# Main.net
KiCad netlist of a schematic drawn in Altium Designer
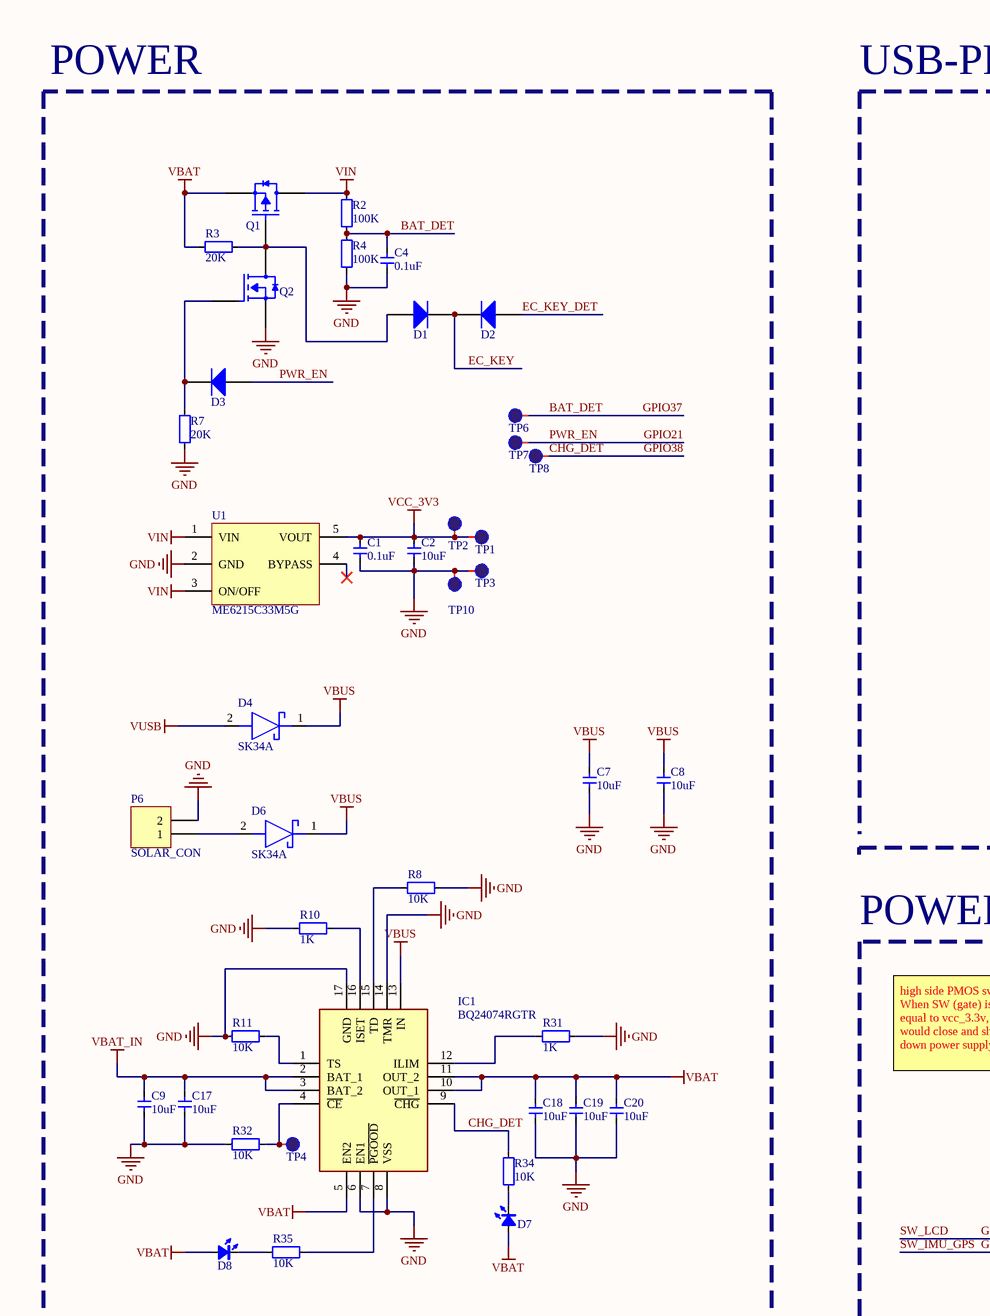
[diagram p0: Main.SchDoc, top left]
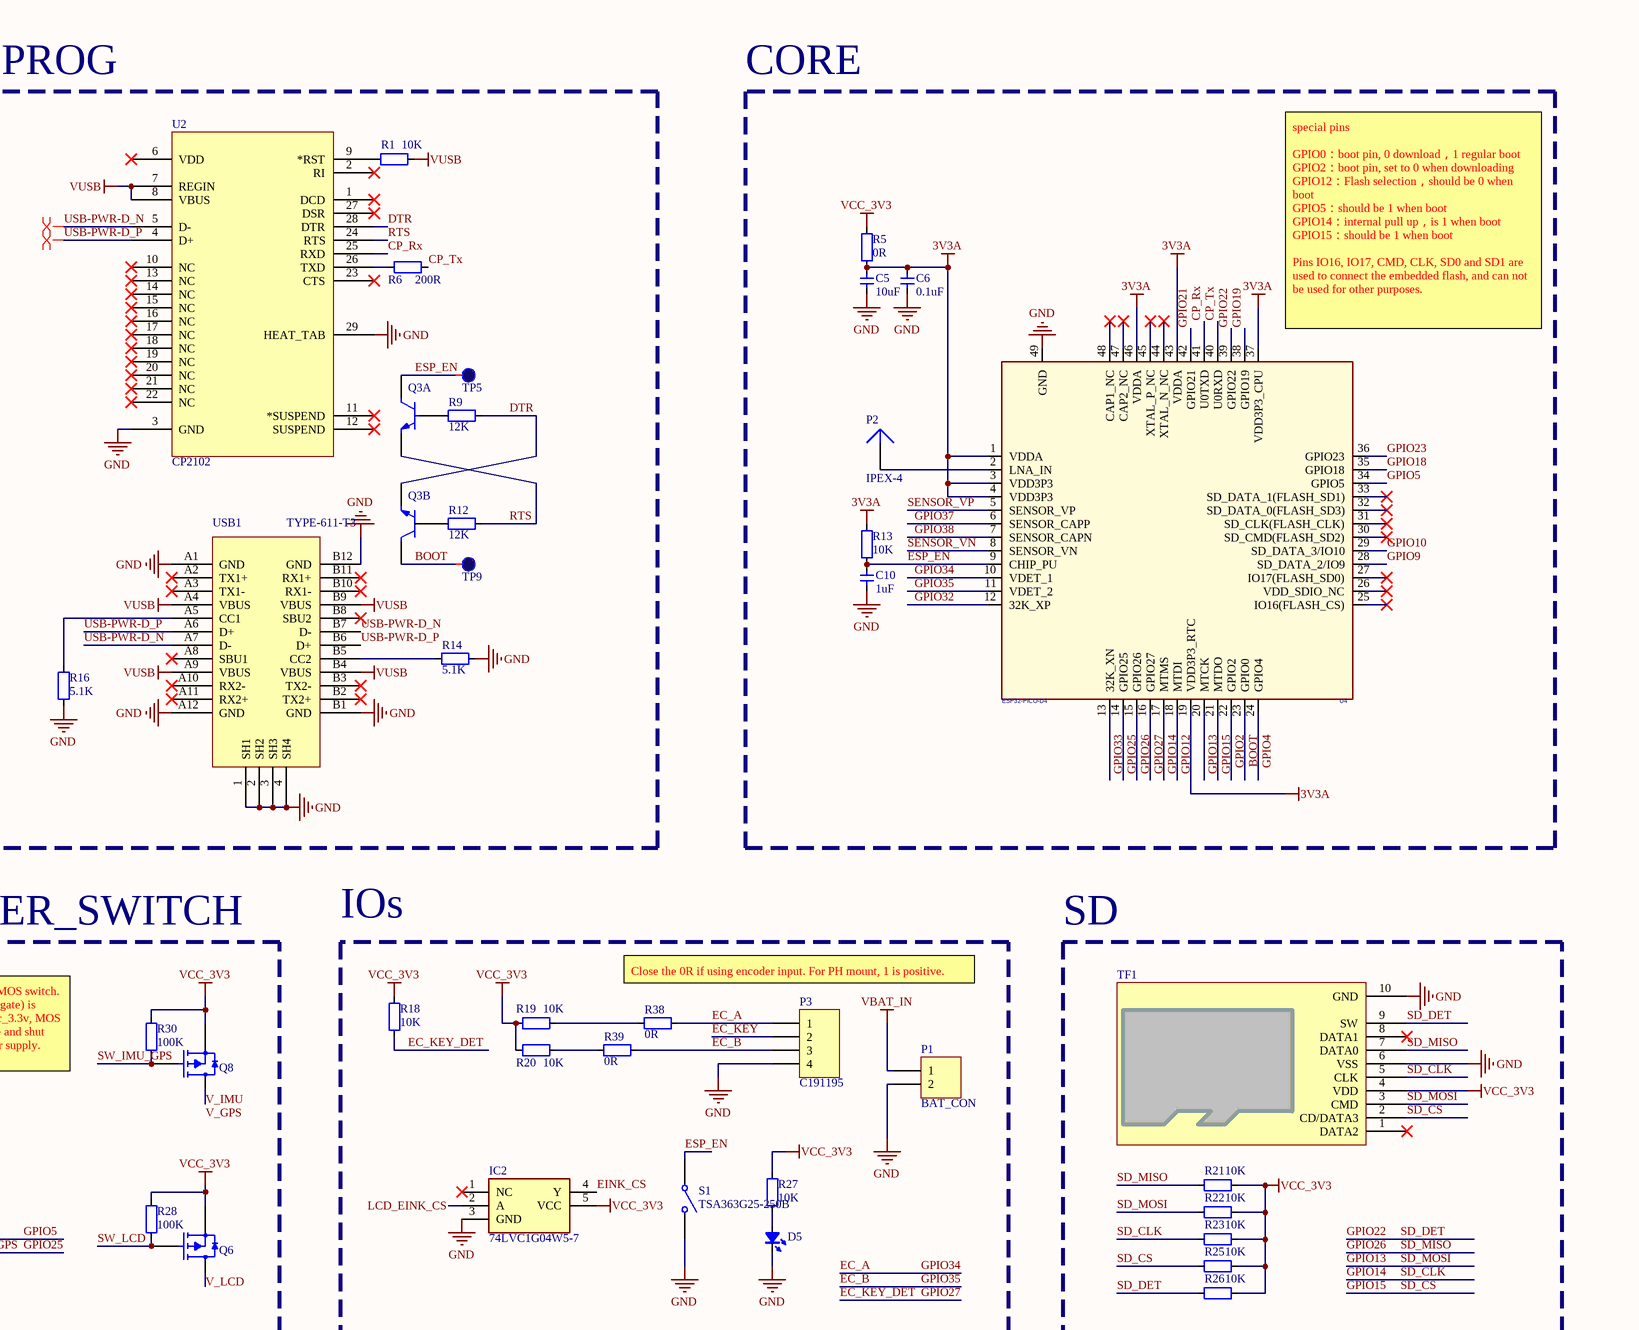
[diagram p1: Main.SchDoc, top right]
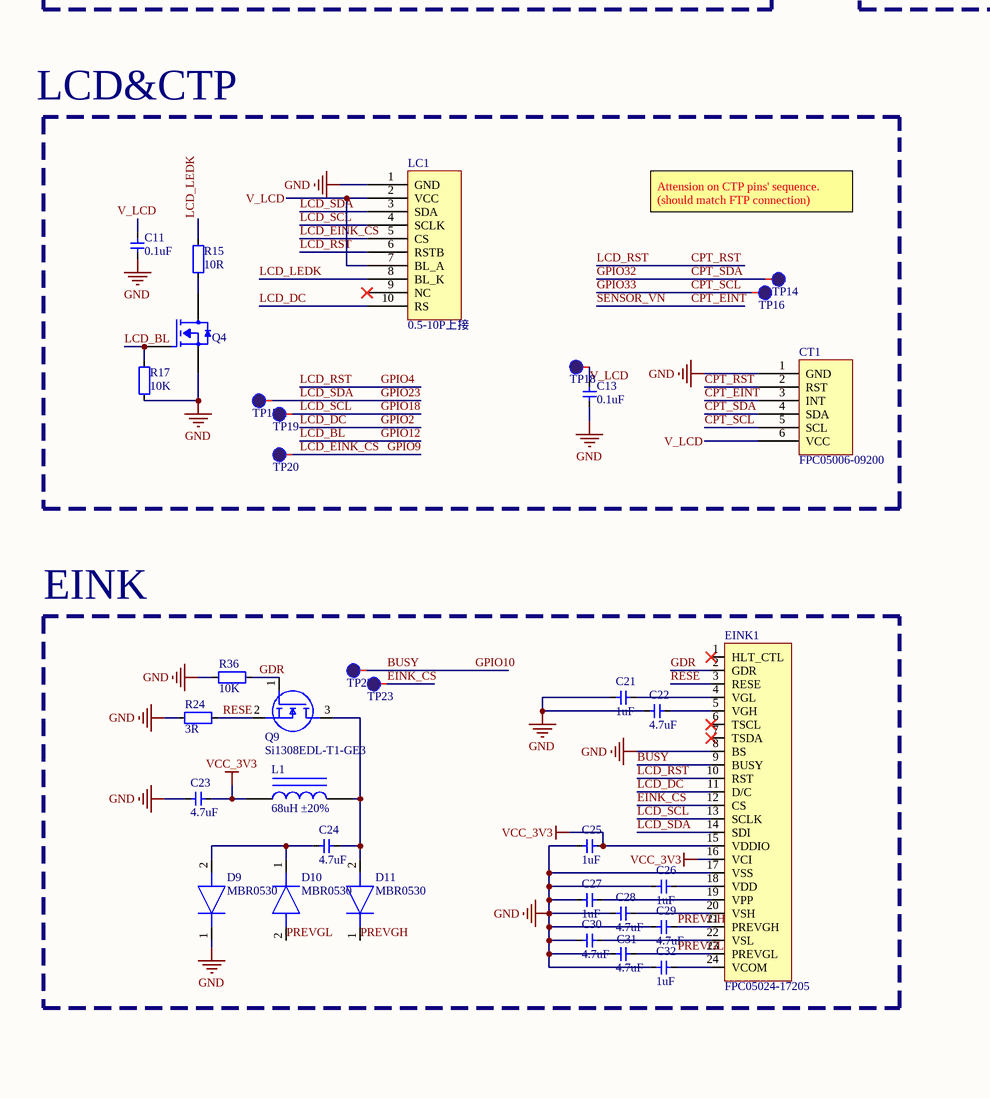
[diagram p2: Main.SchDoc, bottom left]
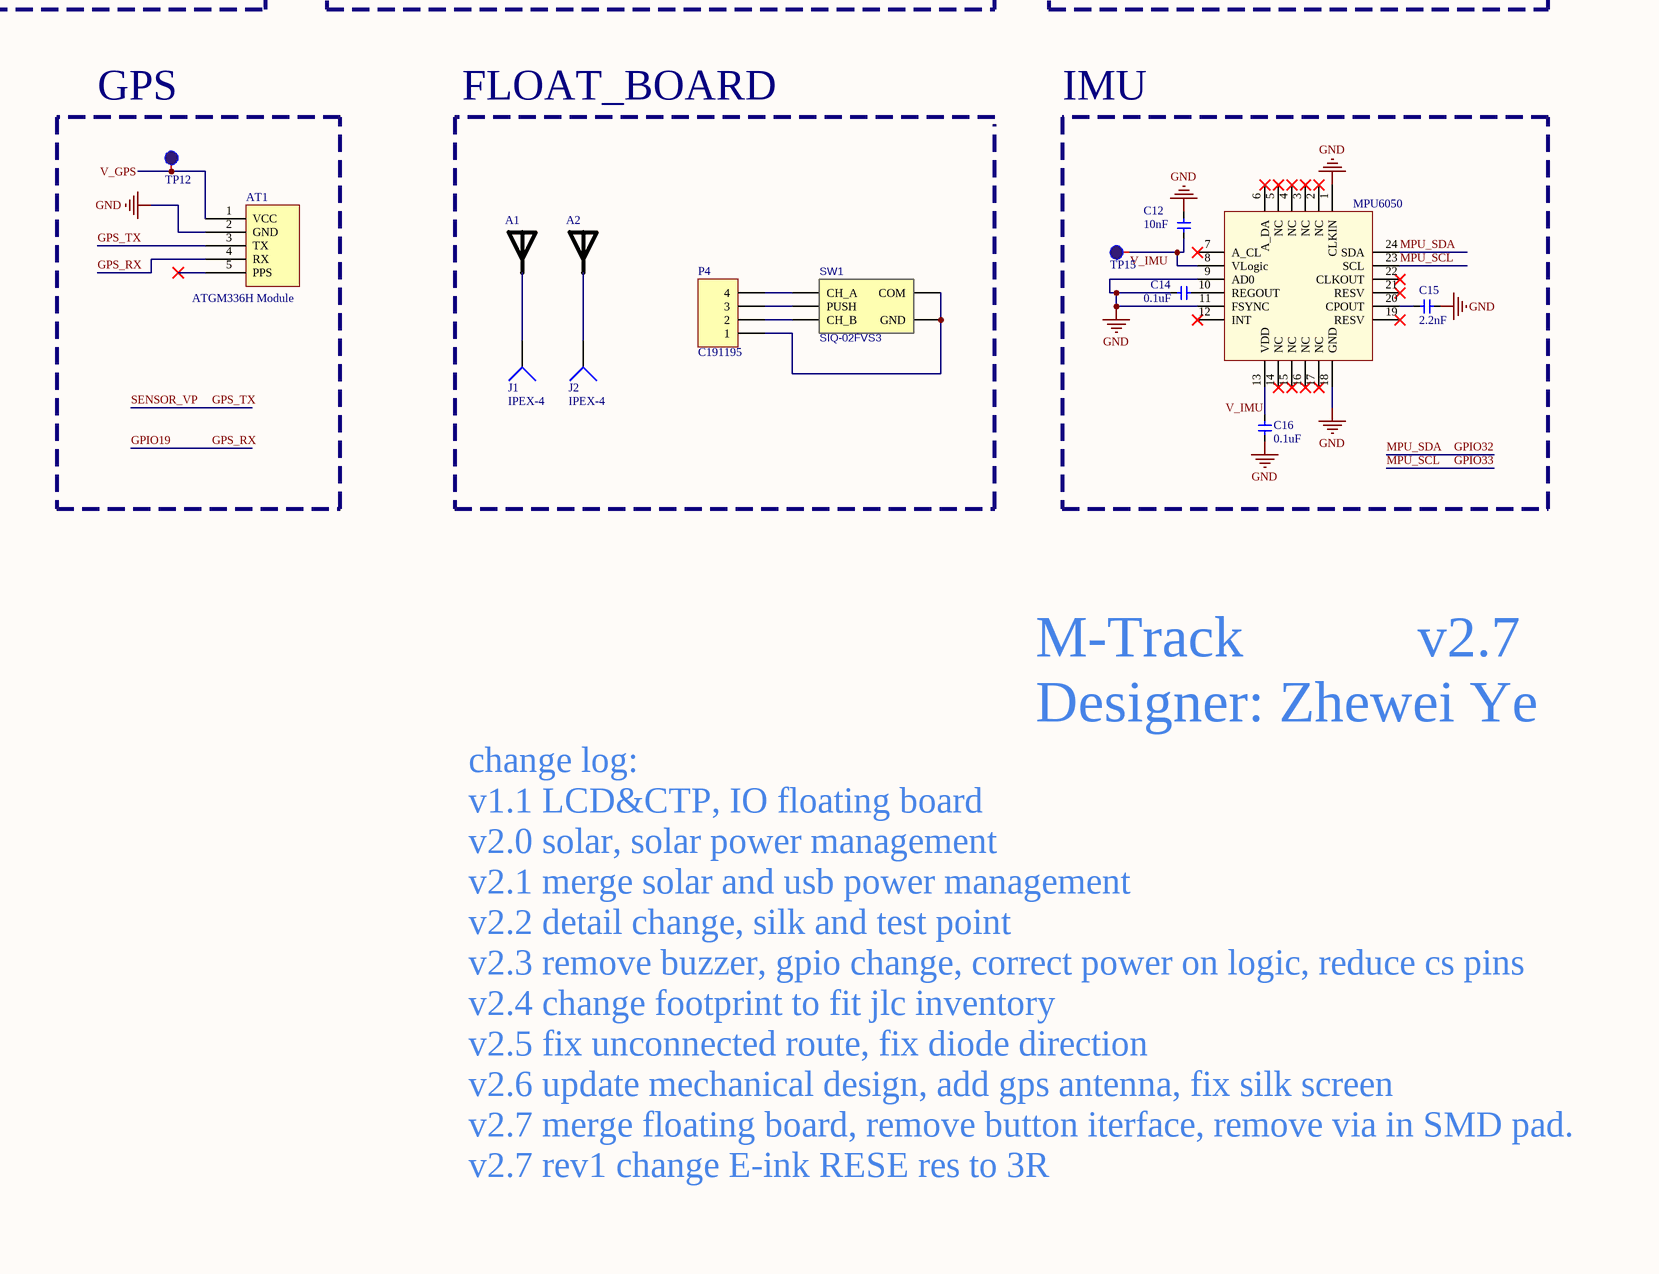
[diagram p3: Main.SchDoc, bottom right]

(export (version "E")
  (design (tool "Eeschema 10.0.6"))
  (components
    (comp (ref "A1")
      (value "AN2051-245")
      (footprint "ANT-Rainsun-AN5120")
      (description "footprint: 2051")
      (fields (field (name "LCSC PART #") "C99727"))
      (libsource (lib "Peak") (part "ANT-Rainsun-AP5120"))
    )
    (comp (ref "A2")
      (value "AN2051-245")
      (footprint "ANT-Rainsun-AN5120")
      (description "footprint: 2051")
      (fields (field (name "LCSC PART #") "C99727"))
      (libsource (lib "Peak") (part "ANT-Rainsun-AP5120"))
    )
    (comp (ref "AT1")
      (value "ATGM336H Module")
      (footprint "PCBComponent_1")
      (libsource (lib "ATGM336H") (part "ATGM336H Module"))
    )
    (comp (ref "C1")
      (value "0.1uF")
      (footprint "CAP_0402")
      (description "Capacitor")
      (libsource (lib "MyPcbLib") (part "电容-0402"))
    )
    (comp (ref "C2")
      (value "10uF")
      (footprint "CAP_0402")
      (description "Capacitor")
      (libsource (lib "MyPcbLib") (part "电容-0402"))
    )
    (comp (ref "C4")
      (value "0.1uF")
      (footprint "CAP_0402")
      (description "Capacitor")
      (libsource (lib "MyPcbLib") (part "电容-0402"))
    )
    (comp (ref "C5")
      (value "10uF")
      (footprint "CAP_0402")
      (description "Capacitor")
      (libsource (lib "MyPcbLib") (part "电容-0402"))
    )
    (comp (ref "C6")
      (value "0.1uF")
      (footprint "CAP_0402")
      (description "Capacitor")
      (libsource (lib "MyPcbLib") (part "电容-0402"))
    )
    (comp (ref "C7")
      (value "10uF")
      (footprint "CAP_0402")
      (description "Capacitor")
      (libsource (lib "MyPcbLib") (part "电容-0402"))
    )
    (comp (ref "C8")
      (value "10uF")
      (footprint "CAP_0402")
      (description "Capacitor")
      (libsource (lib "MyPcbLib") (part "电容-0402"))
    )
    (comp (ref "C9")
      (value "10uF")
      (footprint "CAP_0402")
      (description "Capacitor")
      (libsource (lib "MyPcbLib") (part "电容-0402"))
    )
    (comp (ref "C10")
      (value "1uF")
      (footprint "CAP_0402")
      (description "Capacitor")
      (fields (field (name "LCSC PART #") "C52923"))
      (libsource (lib "MyPcbLib") (part "电容-0402"))
    )
    (comp (ref "C11")
      (value "0.1uF")
      (footprint "CAP_0402")
      (description "Capacitor")
      (libsource (lib "MyPcbLib") (part "电容-0402"))
    )
    (comp (ref "C12")
      (value "10nF")
      (footprint "CAP_0402")
      (description "Capacitor")
      (libsource (lib "MyPcbLib") (part "电容-0402"))
    )
    (comp (ref "C13")
      (value "0.1uF")
      (footprint "CAP_0402")
      (description "Capacitor")
      (libsource (lib "MyPcbLib") (part "电容-0402"))
    )
    (comp (ref "C14")
      (value "0.1uF")
      (footprint "CAP_0402")
      (description "Capacitor")
      (libsource (lib "MyPcbLib") (part "电容-0402"))
    )
    (comp (ref "C15")
      (value "2.2nF")
      (footprint "CAP_0402")
      (description "Capacitor")
      (libsource (lib "MyPcbLib") (part "电容-0402"))
    )
    (comp (ref "C16")
      (value "0.1uF")
      (footprint "CAP_0402")
      (description "Capacitor")
      (libsource (lib "MyPcbLib") (part "电容-0402"))
    )
    (comp (ref "C17")
      (value "10uF")
      (footprint "CAP_0402")
      (description "Capacitor")
      (libsource (lib "MyPcbLib") (part "电容-0402"))
    )
    (comp (ref "C18")
      (value "10uF")
      (footprint "CAP_0402")
      (description "Capacitor")
      (libsource (lib "MyPcbLib") (part "电容-0402"))
    )
    (comp (ref "C19")
      (value "10uF")
      (footprint "CAP_0402")
      (description "Capacitor")
      (libsource (lib "MyPcbLib") (part "电容-0402"))
    )
    (comp (ref "C20")
      (value "10uF")
      (footprint "CAP_0402")
      (description "Capacitor")
      (libsource (lib "MyPcbLib") (part "电容-0402"))
    )
    (comp (ref "C21")
      (value "1uF")
      (footprint "CAP_0402")
      (description "Capacitor")
      (fields (field (name "LCSC PART #") "C52923"))
      (libsource (lib "MyPcbLib") (part "电容-0402"))
    )
    (comp (ref "C22")
      (value "4.7uF")
      (footprint "CAP_0402")
      (description "Capacitor")
      (libsource (lib "MyPcbLib") (part "电容-0402"))
    )
    (comp (ref "C23")
      (value "4.7uF")
      (footprint "CAP_0402")
      (description "Capacitor")
      (libsource (lib "MyPcbLib") (part "电容-0402"))
    )
    (comp (ref "C24")
      (value "4.7uF")
      (footprint "CAP_0402")
      (description "Capacitor")
      (libsource (lib "MyPcbLib") (part "电容-0402"))
    )
    (comp (ref "C25")
      (value "1uF")
      (footprint "CAP_0402")
      (description "Capacitor")
      (fields (field (name "LCSC PART #") "C52923"))
      (libsource (lib "MyPcbLib") (part "电容-0402"))
    )
    (comp (ref "C26")
      (value "1uF")
      (footprint "CAP_0402")
      (description "Capacitor")
      (fields (field (name "LCSC PART #") "C52923"))
      (libsource (lib "MyPcbLib") (part "电容-0402"))
    )
    (comp (ref "C27")
      (value "1uF")
      (footprint "CAP_0402")
      (description "Capacitor")
      (fields (field (name "LCSC PART #") "C52923"))
      (libsource (lib "MyPcbLib") (part "电容-0402"))
    )
    (comp (ref "C28")
      (value "4.7uF")
      (footprint "CAP_0402")
      (description "Capacitor")
      (libsource (lib "MyPcbLib") (part "电容-0402"))
    )
    (comp (ref "C29")
      (value "4.7uF")
      (footprint "CAP_0402")
      (description "Capacitor")
      (libsource (lib "MyPcbLib") (part "电容-0402"))
    )
    (comp (ref "C30")
      (value "4.7uF")
      (footprint "CAP_0402")
      (description "Capacitor")
      (libsource (lib "MyPcbLib") (part "电容-0402"))
    )
    (comp (ref "C31")
      (value "4.7uF")
      (footprint "CAP_0402")
      (description "Capacitor")
      (libsource (lib "MyPcbLib") (part "电容-0402"))
    )
    (comp (ref "C32")
      (value "1uF")
      (footprint "CAP_0402")
      (description "Capacitor")
      (fields (field (name "LCSC PART #") "C52923"))
      (libsource (lib "MyPcbLib") (part "电容-0402"))
    )
    (comp (ref "CT1")
      (value "FPC05006-09200")
      (footprint "FPC0.5-WT-6P")
      (description "下接6p")
      (libsource (lib "Bike_Comp") (part "CTP"))
    )
    (comp (ref "D1")
      (value "B5819W")
      (footprint "SOD-323")
      (description "40V")
      (fields (field (name "LCSC PART #") "C8598"))
      (libsource (lib "MyPcbLib") (part "二极管-5819W"))
    )
    (comp (ref "D2")
      (value "B5819W")
      (footprint "SOD-323")
      (description "40V")
      (fields (field (name "LCSC PART #") "C8598"))
      (libsource (lib "MyPcbLib") (part "二极管-5819W"))
    )
    (comp (ref "D3")
      (value "B5819W")
      (footprint "SOD-323")
      (description "40V")
      (fields (field (name "LCSC PART #") "C8598"))
      (libsource (lib "MyPcbLib") (part "二极管-5819W"))
    )
    (comp (ref "D4")
      (value "SK34A")
      (footprint "SMA")
      (description "GOOD_ARK Schottky Diode")
      (fields
        (field (name "MANUFACTURER_PART_NUMBER") "SK34AFL-TP")
        (field (name "MOUSER PART NUMBER") "833-SK34AFL-TP")
      )
      (libsource (lib "*") (part "SK34AFL-TP"))
    )
    (comp (ref "D5")
      (value "LTST-C281KGKT")
      (footprint "LED_0402_RED")
      (description "GREEN_LED")
      (fields (field (name "LCSC PART #") "C160479"))
      (libsource (lib "") (part "LED_0402_1"))
    )
    (comp (ref "D6")
      (value "SK34A")
      (footprint "SMA")
      (description "GOOD_ARK Schottky Diode")
      (fields
        (field (name "MANUFACTURER_PART_NUMBER") "SK34AFL-TP")
        (field (name "MOUSER PART NUMBER") "833-SK34AFL-TP")
      )
      (libsource (lib "*") (part "SK34AFL-TP"))
    )
    (comp (ref "D7")
      (value "16-213/SDRC/S530-A3/TR8")
      (footprint "LED_0402_RED")
      (description "RED_LED")
      (fields (field (name "LCSC PART #") "C71911"))
      (libsource (lib "KitSprout") (part "LED_0402"))
    )
    (comp (ref "D8")
      (value "LTST-C281KGKT")
      (footprint "LED_0402_RED")
      (description "GREEN_LED")
      (fields (field (name "LCSC PART #") "C160479"))
      (libsource (lib "") (part "LED_0402_2"))
    )
    (comp (ref "D9")
      (value "MBR0530")
      (footprint "SamacSys:SOD3716X135N")
      (description "Diode")
      (fields (field (name "MOUSER PART NUMBER") "512-MBR0530") (field (name "LCSC PART #") "C77336"))
      (libsource (lib "*") (part "MBR0530"))
    )
    (comp (ref "D10")
      (value "MBR0530")
      (footprint "SamacSys:SOD3716X135N")
      (description "Diode")
      (fields (field (name "MOUSER PART NUMBER") "512-MBR0530") (field (name "LCSC PART #") "C77336"))
      (libsource (lib "*") (part "MBR0530"))
    )
    (comp (ref "D11")
      (value "MBR0530")
      (footprint "SamacSys:SOD3716X135N")
      (description "Diode")
      (fields (field (name "MOUSER PART NUMBER") "512-MBR0530") (field (name "LCSC PART #") "C77336"))
      (libsource (lib "*") (part "MBR0530"))
    )
    (comp (ref "EINK1")
      (value "FPC05024-17205")
      (footprint "FPC0.5-WT-24P")
      (description "上接24p")
      (libsource (lib "Bike_Comp") (part "EINK"))
    )
    (comp (ref "IC1")
      (value "BQ24074RGTR")
      (footprint "SamacSys:QFN50P300X300X100-17N-D")
      (description "Integrated Circuit")
      (fields (field (name "MOUSER PART NUMBER") "595-BQ24074RGTR"))
      (libsource (lib "*") (part "BQ24074RGTR"))
    )
    (comp (ref "IC2")
      (value "74LVC1G04W5-7")
      (footprint "SamacSys:SOT95P285X140-5N")
      (description "Integrated Circuit")
      (fields (field (name "MOUSER PART NUMBER") "621-74LVC1G04W5-7"))
      (libsource (lib "*") (part "74LVC1G04W5-7"))
    )
    (comp (ref "J1")
      (value "IPEX-4")
      (footprint "COAXIAL/SMD/CON/V/I-PEX/W08-5801")
      (description "Socket")
      (fields (field (name "PUBLISHER") "Altium Limited"))
      (libsource (lib "Miscellaneous Connectors") (part "Socket"))
    )
    (comp (ref "J2")
      (value "IPEX-4")
      (footprint "COAXIAL/SMD/CON/V/I-PEX/W08-5801")
      (description "Socket")
      (fields (field (name "PUBLISHER") "Altium Limited"))
      (libsource (lib "Miscellaneous Connectors") (part "Socket"))
    )
    (comp (ref "L1")
      (value "68uH ±20%")
      (footprint "SWPA3015")
      (description "Magnetic-Core Inductor")
      (fields (field (name "LCSC PART #") "C2925423") (field (name "PUBLISHER") "Altium Limited"))
      (libsource (lib "Miscellaneous Devices") (part "Inductor Iron"))
    )
    (comp (ref "LC1")
      (value "0.5-10P上接")
      (footprint "FPC0.5-WT-10P")
      (description "上接10p")
      (fields (field (name "LCSC PART #") "C11085"))
      (libsource (lib "Bike_Comp") (part "LCD"))
    )
    (comp (ref "P1")
      (value "BAT_CON")
      (footprint "PH2.0-W-2P")
      (description "PH2.0-2P-LT")
      (fields (field (name "PUBLISHER") "Altium Limited"))
      (libsource (lib "Miscellaneous Connectors") (part "Header 2"))
    )
    (comp (ref "P2")
      (value "IPEX-4")
      (footprint "COAXIAL/SMD/CON/V/I-PEX/W08-5801")
      (description "Plug")
      (fields (field (name "PUBLISHER") "Altium Limited"))
      (libsource (lib "Miscellaneous Connectors") (part "Plug"))
    )
    (comp (ref "P3")
      (value "C191195")
      (footprint "FPC0.5-WT-4P")
      (description "Header, 4-Pin")
      (fields (field (name "PUBLISHER") "Altium Limited"))
      (libsource (lib "Miscellaneous Connectors") (part "Header 4"))
    )
    (comp (ref "P4")
      (value "C191195")
      (footprint "FPC0.5-WT-4P")
      (description "Header, 4-Pin")
      (fields (field (name "PUBLISHER") "Altium Limited"))
      (libsource (lib "") (part "Header 4_1"))
    )
    (comp (ref "P6")
      (value "SOLAR_CON")
      (footprint "PH2.0-W-2P")
      (description "PH2.0-2P-LT")
      (fields (field (name "PUBLISHER") "Altium Limited"))
      (libsource (lib "") (part "Header 2_1"))
    )
    (comp (ref "Q1")
      (value "AO3401A")
      (footprint "SOT23-3")
      (description "P-MOS")
      (fields (field (name "LCSC PART #") "C15127"))
      (libsource (lib "MyPcbLib") (part "AO3401A"))
    )
    (comp (ref "Q2")
      (value "AO3400A")
      (footprint "SOT23-3")
      (description "N-MOS")
      (libsource (lib "MyPcbLib") (part "AO3400A"))
    )
    (comp (ref "Q3")
      (value "EMX1T2R")
      (footprint "SOT563-6")
      (libsource (lib "MyPcbLib") (part "BC847BVC-7"))
    )
    (comp (ref "Q4")
      (value "AO3400A")
      (footprint "SOT23-3")
      (description "N-MOS")
      (libsource (lib "Bike_Comp") (part "AO3400A"))
    )
    (comp (ref "Q6")
      (value "AO3401A")
      (footprint "SOT23-3")
      (description "P-MOS")
      (fields (field (name "LCSC PART #") "C15127"))
      (libsource (lib "MyPcbLib") (part "AO3401A"))
    )
    (comp (ref "Q8")
      (value "AO3401A")
      (footprint "SOT23-3")
      (description "P-MOS")
      (fields (field (name "LCSC PART #") "C15127"))
      (libsource (lib "MyPcbLib") (part "AO3401A"))
    )
    (comp (ref "Q9")
      (value "Si1308EDL-T1-GE3")
      (footprint "SamacSys:SOT65P210X110-3N")
      (description "MOSFET (N-Channel)")
      (fields
        (field (name "MOUSER PART NUMBER") "78-SI1308EDL-T1-GE3")
        (field (name "ARROW PART NUMBER") "SI1308EDL-T1-GE3")
      )
      (libsource (lib "*") (part "Si1308EDL-T1-GE3"))
    )
    (comp (ref "R1")
      (value "10K")
      (footprint "RES_0402")
      (description "Resistor")
      (libsource (lib "") (part "电阻-0402_2"))
    )
    (comp (ref "R2")
      (value "100K")
      (footprint "RES_0402")
      (description "Resistor")
      (libsource (lib "") (part "电阻-0402_1"))
    )
    (comp (ref "R3")
      (value "20K")
      (footprint "RES_0402")
      (description "Resistor")
      (libsource (lib "") (part "电阻-0402_3"))
    )
    (comp (ref "R4")
      (value "100K")
      (footprint "RES_0402")
      (description "Resistor")
      (libsource (lib "") (part "电阻-0402_1"))
    )
    (comp (ref "R5")
      (value "0R")
      (footprint "RES_0402")
      (description "Resistor")
      (libsource (lib "MyPcbLib") (part "电阻-0402"))
    )
    (comp (ref "R6")
      (value "200R")
      (footprint "RES_0402")
      (description "Resistor")
      (libsource (lib "") (part "电阻-0402_2"))
    )
    (comp (ref "R7")
      (value "20K")
      (footprint "RES_0402")
      (description "Resistor")
      (libsource (lib "") (part "电阻-0402_1"))
    )
    (comp (ref "R8")
      (value "10K")
      (footprint "RES_0402")
      (description "Resistor")
      (libsource (lib "") (part "电阻-0402_2"))
    )
    (comp (ref "R9")
      (value "12K")
      (footprint "RES_0402")
      (description "Resistor")
      (fields (field (name "LCSC PART #") "C25752"))
      (libsource (lib "") (part "电阻-0402_2"))
    )
    (comp (ref "R10")
      (value "1K")
      (footprint "RES_0402")
      (description "Resistor")
      (libsource (lib "") (part "电阻-0402_3"))
    )
    (comp (ref "R11")
      (value "10K")
      (footprint "RES_0402")
      (description "Resistor")
      (libsource (lib "") (part "电阻-0402_2"))
    )
    (comp (ref "R12")
      (value "12K")
      (footprint "RES_0402")
      (description "Resistor")
      (fields (field (name "LCSC PART #") "C25752"))
      (libsource (lib "") (part "电阻-0402_2"))
    )
    (comp (ref "R13")
      (value "10K")
      (footprint "RES_0402")
      (description "Resistor")
      (libsource (lib "MyPcbLib") (part "电阻-0402"))
    )
    (comp (ref "R14")
      (value "5.1K")
      (footprint "RES_0402")
      (description "Resistor")
      (libsource (lib "") (part "电阻-0402_2"))
    )
    (comp (ref "R15")
      (value "10R")
      (footprint "RES_0402")
      (description "Resistor")
      (fields (field (name "LCSC PART #") "C25077"))
      (libsource (lib "") (part "电阻-0402_1"))
    )
    (comp (ref "R16")
      (value "5.1K")
      (footprint "RES_0402")
      (description "Resistor")
      (libsource (lib "MyPcbLib") (part "电阻-0402"))
    )
    (comp (ref "R17")
      (value "10K")
      (footprint "RES_0402")
      (description "Resistor")
      (libsource (lib "") (part "电阻-0402_1"))
    )
    (comp (ref "R18")
      (value "10K")
      (footprint "RES_0402")
      (description "Resistor")
      (libsource (lib "MyPcbLib") (part "电阻-0402"))
    )
    (comp (ref "R19")
      (value "10K")
      (footprint "RES_0402")
      (description "Resistor")
      (libsource (lib "") (part "电阻-0402_2"))
    )
    (comp (ref "R20")
      (value "10K")
      (footprint "RES_0402")
      (description "Resistor")
      (libsource (lib "") (part "电阻-0402_2"))
    )
    (comp (ref "R21")
      (value "10K")
      (footprint "RES_0402")
      (description "Resistor")
      (libsource (lib "") (part "电阻-0402_2"))
    )
    (comp (ref "R22")
      (value "10K")
      (footprint "RES_0402")
      (description "Resistor")
      (libsource (lib "") (part "电阻-0402_2"))
    )
    (comp (ref "R23")
      (value "10K")
      (footprint "RES_0402")
      (description "Resistor")
      (libsource (lib "") (part "电阻-0402_2"))
    )
    (comp (ref "R24")
      (value "3R")
      (footprint "RES_0402")
      (description "Resistor")
      (libsource (lib "") (part "电阻-0402_3"))
    )
    (comp (ref "R25")
      (value "10K")
      (footprint "RES_0402")
      (description "Resistor")
      (libsource (lib "") (part "电阻-0402_2"))
    )
    (comp (ref "R26")
      (value "10K")
      (footprint "RES_0402")
      (description "Resistor")
      (libsource (lib "") (part "电阻-0402_2"))
    )
    (comp (ref "R27")
      (value "10K")
      (footprint "RES_0402")
      (description "Resistor")
      (libsource (lib "") (part "电阻-0402_1"))
    )
    (comp (ref "R28")
      (value "100K")
      (footprint "RES_0402")
      (description "Resistor")
      (libsource (lib "") (part "电阻-0402_1"))
    )
    (comp (ref "R30")
      (value "100K")
      (footprint "RES_0402")
      (description "Resistor")
      (libsource (lib "") (part "电阻-0402_1"))
    )
    (comp (ref "R31")
      (value "1K")
      (footprint "RES_0402")
      (description "Resistor")
      (libsource (lib "") (part "电阻-0402_2"))
    )
    (comp (ref "R32")
      (value "10K")
      (footprint "RES_0402")
      (description "Resistor")
      (libsource (lib "") (part "电阻-0402_2"))
    )
    (comp (ref "R34")
      (value "10K")
      (footprint "RES_0402")
      (description "Resistor")
      (libsource (lib "") (part "电阻-0402_1"))
    )
    (comp (ref "R35")
      (value "10K")
      (footprint "RES_0402")
      (description "Resistor")
      (libsource (lib "") (part "电阻-0402_3"))
    )
    (comp (ref "R36")
      (value "10K")
      (footprint "RES_0402")
      (description "Resistor")
      (libsource (lib "") (part "电阻-0402_3"))
    )
    (comp (ref "R38")
      (value "0R")
      (footprint "RES_0402")
      (description "Resistor")
      (libsource (lib "") (part "电阻-0402_3"))
    )
    (comp (ref "R39")
      (value "0R")
      (footprint "RES_0402")
      (description "Resistor")
      (libsource (lib "") (part "电阻-0402_3"))
    )
    (comp (ref "S1")
      (value "TSA363G25-250B")
      (footprint "SW SMD-3*6*2.5")
      (description "Single-Pole, Single-Throw Switch")
      (fields (field (name "PUBLISHER") "Altium Limited"))
      (libsource (lib "Miscellaneous Devices") (part "SW-SPST"))
    )
    (comp (ref "SW1")
      (value "SIQ-02FVS3")
      (footprint "SIQ-02FVS3")
      (description "Rotary Encoder")
      (fields
        (field (name "BOM_SUPPLIER PART") "C1322543")
        (field (name "BOM_MANUFACTURER PART") "EC11E1534443")
        (field (name "CONTRIBUTOR") "LCSC")
      )
      (libsource (lib "MyPcbLib") (part "Rotary Encoder"))
    )
    (comp (ref "TF1")
      (value "TF-012D")
      (footprint "TF-SOCKET")
      (description "8脚自弹")
      (libsource (lib "MyPcbLib") (part "TF卡座"))
    )
    (comp (ref "TP1") (value "TP") (footprint "TP_SMD") (libsource (lib "BSPD_2019_V3") (part "TP")))
    (comp (ref "TP2") (value "TP") (footprint "TEST 1") (libsource (lib "BSPD_2019_V3") (part "TP")))
    (comp (ref "TP3") (value "TP") (footprint "TP_SMD") (libsource (lib "BSPD_2019_V3") (part "TP")))
    (comp (ref "TP4") (value "TP") (footprint "TEST 1") (libsource (lib "Bike_Comp") (part "TP")))
    (comp (ref "TP5") (value "TP") (footprint "TEST 1") (libsource (lib "Bike_Comp") (part "TP")))
    (comp (ref "TP6") (value "TP") (footprint "TEST 1") (libsource (lib "Bike_Comp") (part "TP")))
    (comp (ref "TP7") (value "TP") (footprint "TEST 1") (libsource (lib "Bike_Comp") (part "TP")))
    (comp (ref "TP8") (value "TP") (footprint "TEST 1") (libsource (lib "Bike_Comp") (part "TP")))
    (comp (ref "TP9") (value "TP") (footprint "TEST 1") (libsource (lib "Bike_Comp") (part "TP")))
    (comp (ref "TP10") (value "TP") (footprint "TP_SMD") (libsource (lib "BSPD_2019_V3") (part "TP")))
    (comp (ref "TP12") (value "TP") (footprint "TEST 1") (libsource (lib "Bike_Comp") (part "TP")))
    (comp (ref "TP14") (value "TP") (footprint "TEST 1") (libsource (lib "Bike_Comp") (part "TP")))
    (comp (ref "TP15") (value "TP") (footprint "TEST 1") (libsource (lib "Bike_Comp") (part "TP")))
    (comp (ref "TP16") (value "TP") (footprint "TEST 1") (libsource (lib "Bike_Comp") (part "TP")))
    (comp (ref "TP17") (value "TP") (footprint "TEST 1") (libsource (lib "Bike_Comp") (part "TP")))
    (comp (ref "TP18") (value "TP") (footprint "TEST 1") (libsource (lib "Bike_Comp") (part "TP")))
    (comp (ref "TP19") (value "TP") (footprint "TEST 1") (libsource (lib "Bike_Comp") (part "TP")))
    (comp (ref "TP20") (value "TP") (footprint "TEST 1") (libsource (lib "Bike_Comp") (part "TP")))
    (comp (ref "TP22") (value "TP") (footprint "TEST 1") (libsource (lib "Bike_Comp") (part "TP")))
    (comp (ref "TP23") (value "TP") (footprint "TEST 1") (libsource (lib "Bike_Comp") (part "TP")))
    (comp (ref "U1")
      (value "ME6215C33M5G")
      (footprint "SOT23-5")
      (description "LDO module changed, BYPASS now is NC")
      (libsource (lib "mLib") (part "LP2992"))
    )
    (comp (ref "U2")
      (value "CP2102")
      (footprint "QFN-28")
      (description "USB转TTL")
      (libsource (lib "mLib") (part "CP2102"))
    )
    (comp (ref "U4")
      (value "ESP32-PICO-D4")
      (footprint "QFN-48_7X7")
      (fields (field (name "LCSC PART #") "C193707"))
      (libsource (lib "Peak") (part "ESP32-PICO"))
    )
    (comp (ref "U5")
      (value "MPU6050")
      (footprint "QFN-24")
      (description "六轴传感器")
      (fields (field (name "LCSC PART #") "C24112"))
      (libsource (lib "mLib") (part "MPU6050"))
    )
    (comp (ref "USB1")
      (value "TYPE-611-T3")
      (footprint "USB-C-SMD_16P")
      (description "16pin")
      (libsource (lib "MyPcbLib") (part "USB-Type-C-TOP"))
    )
  )
  (nets
    (net (code "1") (name "/BAT_DET") (class "Default")
      (node (ref "C4") (pin "2") (pinfunction "2_2") (pintype "passive"))
      (node (ref "R2") (pin "1") (pinfunction "1_1") (pintype "passive"))
      (node (ref "R4") (pin "2") (pinfunction "2_2") (pintype "passive"))
      (node (ref "TP6") (pin "0") (pinfunction "0_0") (pintype "passive"))
      (node (ref "U4") (pin "6") (pinfunction "SENSOR_CAPP_6") (pintype "passive"))
    )
    (net (code "2") (name "/BOOT") (class "Default")
      (node (ref "Q3") (pin "3") (pinfunction "C2_3") (pintype "passive"))
      (node (ref "TP9") (pin "0") (pinfunction "0_0") (pintype "passive"))
      (node (ref "U4") (pin "23") (pinfunction "GPIO0_23") (pintype "passive"))
    )
    (net (code "3") (name "/BUSY") (class "Default")
      (node (ref "EINK1") (pin "9") (pinfunction "BUSY_9") (pintype "passive"))
      (node (ref "TP22") (pin "0") (pinfunction "0_0") (pintype "passive"))
      (node (ref "U4") (pin "29") (pinfunction "SD_DATA_3/IO10_29") (pintype "passive"))
    )
    (net (code "4") (name "/CHG_DET") (class "Default")
      (node (ref "IC1") (pin "9") (pinfunction "~{CHG}_9") (pintype "passive"))
      (node (ref "R34") (pin "2") (pinfunction "2_2") (pintype "passive"))
      (node (ref "TP8") (pin "0") (pinfunction "0_0") (pintype "passive"))
      (node (ref "U4") (pin "7") (pinfunction "SENSOR_CAPN_7") (pintype "passive"))
    )
    (net (code "5") (name "/CPT_EINT") (class "Default")
      (node (ref "CT1") (pin "3") (pinfunction "INT_3") (pintype "passive"))
      (node (ref "U4") (pin "8") (pinfunction "SENSOR_VN_8") (pintype "passive"))
    )
    (net (code "6") (name "/CPT_RST") (class "Default")
      (node (ref "CT1") (pin "2") (pinfunction "RST_2") (pintype "passive"))
      (node (ref "EINK1") (pin "10") (pinfunction "RST_10") (pintype "passive"))
      (node (ref "LC1") (pin "6") (pinfunction "RSTB_6") (pintype "passive"))
      (node (ref "U4") (pin "24") (pinfunction "GPIO4_24") (pintype "passive"))
    )
    (net (code "7") (name "/CPT_SCL") (class "Default")
      (node (ref "CT1") (pin "5") (pinfunction "SCL_5") (pintype "passive"))
      (node (ref "TP16") (pin "0") (pinfunction "0_0") (pintype "passive"))
      (node (ref "U4") (pin "13") (pinfunction "32K_XN_13") (pintype "passive"))
      (node (ref "U5") (pin "23") (pinfunction "SCL_23") (pintype "passive"))
    )
    (net (code "8") (name "/CPT_SDA") (class "Default")
      (node (ref "CT1") (pin "4") (pinfunction "SDA_4") (pintype "passive"))
      (node (ref "TP14") (pin "0") (pinfunction "0_0") (pintype "passive"))
      (node (ref "U4") (pin "12") (pinfunction "32K_XP_12") (pintype "passive"))
      (node (ref "U5") (pin "24") (pinfunction "SDA_24") (pintype "passive"))
    )
    (net (code "9") (name "/CP_Rx") (class "Default")
      (node (ref "U2") (pin "25") (pinfunction "RXD_25") (pintype "passive"))
      (node (ref "U4") (pin "41") (pinfunction "U0TXD_41") (pintype "power_in"))
    )
    (net (code "10") (name "/CP_Tx") (class "Default")
      (node (ref "R6") (pin "1") (pinfunction "1_1") (pintype "passive"))
      (node (ref "U4") (pin "40") (pinfunction "U0RXD_40") (pintype "power_in"))
    )
    (net (code "11") (name "/DTR") (class "Default")
      (node (ref "Q3") (pin "4") (pinfunction "E2_4") (pintype "passive"))
      (node (ref "R9") (pin "1") (pinfunction "1_1") (pintype "passive"))
      (node (ref "U2") (pin "28") (pinfunction "DTR_28") (pintype "passive"))
    )
    (net (code "12") (name "/EC_A") (class "Default")
      (node (ref "P3") (pin "1") (pinfunction "1_1") (pintype "passive"))
      (node (ref "R38") (pin "2") (pinfunction "2_2") (pintype "passive"))
      (node (ref "U4") (pin "10") (pinfunction "VDET_1_10") (pintype "passive"))
    )
    (net (code "13") (name "/EC_B") (class "Default")
      (node (ref "P3") (pin "3") (pinfunction "3_3") (pintype "passive"))
      (node (ref "R39") (pin "2") (pinfunction "2_2") (pintype "passive"))
      (node (ref "U4") (pin "11") (pinfunction "VDET_2_11") (pintype "passive"))
    )
    (net (code "14") (name "/EC_KEY") (class "Default")
      (node (ref "D1") (pin "2") (pinfunction "K_2") (pintype "passive"))
      (node (ref "D2") (pin "2") (pinfunction "K_2") (pintype "passive"))
      (node (ref "P3") (pin "2") (pinfunction "2_2") (pintype "passive"))
    )
    (net (code "15") (name "/EC_KEY_DET") (class "Default")
      (node (ref "D2") (pin "1") (pinfunction "A_1") (pintype "passive"))
      (node (ref "R18") (pin "2") (pinfunction "2_2") (pintype "passive"))
      (node (ref "U4") (pin "16") (pinfunction "GPIO27_16") (pintype "passive"))
    )
    (net (code "16") (name "/EINK_CS") (class "Default")
      (node (ref "EINK1") (pin "12") (pinfunction "CS_12") (pintype "passive"))
      (node (ref "IC2") (pin "4") (pinfunction "Y_4") (pintype "passive"))
      (node (ref "TP23") (pin "0") (pinfunction "0_0") (pintype "passive"))
    )
    (net (code "17") (name "/ESP_EN") (class "Default")
      (node (ref "C10") (pin "1") (pinfunction "1_1") (pintype "passive"))
      (node (ref "Q3") (pin "6") (pinfunction "C1_6") (pintype "passive"))
      (node (ref "R13") (pin "2") (pinfunction "2_2") (pintype "passive"))
      (node (ref "S1") (pin "1") (pinfunction "COMMON_1") (pintype "passive"))
      (node (ref "TP5") (pin "0") (pinfunction "0_0") (pintype "passive"))
      (node (ref "U4") (pin "9") (pinfunction "CHIP_PU_9") (pintype "passive"))
    )
    (net (code "18") (name "/GDR") (class "Default")
      (node (ref "EINK1") (pin "2") (pinfunction "GDR_2") (pintype "passive"))
      (node (ref "Q9") (pin "1") (pinfunction "G_1") (pintype "passive"))
      (node (ref "R36") (pin "2") (pinfunction "2_2") (pintype "passive"))
    )
    (net (code "19") (name "/GPIO2") (class "Default")
      (node (ref "EINK1") (pin "11") (pinfunction "D/C_11") (pintype "passive"))
      (node (ref "LC1") (pin "10") (pinfunction "RS_10") (pintype "passive"))
      (node (ref "U4") (pin "22") (pinfunction "GPIO2_22") (pintype "passive"))
    )
    (net (code "20") (name "/GPIO5") (class "Default")
      (node (ref "Q6") (pin "1") (pinfunction "G_1") (pintype "passive"))
      (node (ref "R28") (pin "1") (pinfunction "1_1") (pintype "passive"))
      (node (ref "U4") (pin "34") (pinfunction "GPIO5_34") (pintype "passive"))
    )
    (net (code "21") (name "/GPIO9") (class "Default")
      (node (ref "IC2") (pin "2") (pinfunction "A_2") (pintype "passive"))
      (node (ref "LC1") (pin "5") (pinfunction "CS_5") (pintype "passive"))
      (node (ref "TP20") (pin "0") (pinfunction "0_0") (pintype "passive"))
      (node (ref "U4") (pin "28") (pinfunction "SD_DATA_2/IO9_28") (pintype "passive"))
    )
    (net (code "22") (name "/GPIO12") (class "Default")
      (node (ref "Q4") (pin "1") (pinfunction "G_1") (pintype "passive"))
      (node (ref "R17") (pin "2") (pinfunction "2_2") (pintype "passive"))
      (node (ref "U4") (pin "18") (pinfunction "MTDI_18") (pintype "passive"))
    )
    (net (code "23") (name "/GPIO13") (class "Default")
      (node (ref "R22") (pin "2") (pinfunction "2_2") (pintype "passive"))
      (node (ref "TF1") (pin "3") (pinfunction "CMD_3") (pintype "passive"))
      (node (ref "U4") (pin "20") (pinfunction "MTCK_20") (pintype "passive"))
    )
    (net (code "24") (name "/GPIO14") (class "Default")
      (node (ref "R23") (pin "2") (pinfunction "2_2") (pintype "passive"))
      (node (ref "TF1") (pin "5") (pinfunction "CLK_5") (pintype "passive"))
      (node (ref "U4") (pin "17") (pinfunction "MTMS_17") (pintype "passive"))
    )
    (net (code "25") (name "/GPIO15") (class "Default")
      (node (ref "R25") (pin "2") (pinfunction "2_2") (pintype "passive"))
      (node (ref "TF1") (pin "2") (pinfunction "CD/DATA3_2") (pintype "passive"))
      (node (ref "U4") (pin "21") (pinfunction "MTDO_21") (pintype "passive"))
    )
    (net (code "26") (name "/GPIO18") (class "Default")
      (node (ref "EINK1") (pin "13") (pinfunction "SCLK_13") (pintype "passive"))
      (node (ref "LC1") (pin "4") (pinfunction "SCLK_4") (pintype "passive"))
      (node (ref "TP19") (pin "0") (pinfunction "0_0") (pintype "passive"))
      (node (ref "U4") (pin "35") (pinfunction "GPIO18_35") (pintype "passive"))
    )
    (net (code "27") (name "/GPIO19") (class "Default")
      (node (ref "AT1") (pin "4") (pinfunction "RX_4") (pintype "passive"))
      (node (ref "U4") (pin "38") (pinfunction "GPIO19_38") (pintype "passive"))
    )
    (net (code "28") (name "/GPIO21") (class "Default")
      (node (ref "D3") (pin "1") (pinfunction "A_1") (pintype "passive"))
      (node (ref "TP7") (pin "0") (pinfunction "0_0") (pintype "passive"))
      (node (ref "U4") (pin "42") (pinfunction "GPIO21_42") (pintype "passive"))
    )
    (net (code "29") (name "/GPIO22") (class "Default")
      (node (ref "R26") (pin "2") (pinfunction "2_2") (pintype "passive"))
      (node (ref "TF1") (pin "9") (pinfunction "SW_9") (pintype "passive"))
      (node (ref "U4") (pin "39") (pinfunction "GPIO22_39") (pintype "passive"))
    )
    (net (code "30") (name "/GPIO23") (class "Default")
      (node (ref "EINK1") (pin "14") (pinfunction "SDI_14") (pintype "passive"))
      (node (ref "LC1") (pin "3") (pinfunction "SDA_3") (pintype "passive"))
      (node (ref "TP17") (pin "0") (pinfunction "0_0") (pintype "passive"))
      (node (ref "U4") (pin "36") (pinfunction "GPIO23_36") (pintype "passive"))
    )
    (net (code "31") (name "/GPIO25") (class "Default")
      (node (ref "Q8") (pin "1") (pinfunction "G_1") (pintype "passive"))
      (node (ref "R30") (pin "1") (pinfunction "1_1") (pintype "passive"))
      (node (ref "U4") (pin "14") (pinfunction "GPIO25_14") (pintype "passive"))
    )
    (net (code "32") (name "/GPIO26") (class "Default")
      (node (ref "R21") (pin "2") (pinfunction "2_2") (pintype "passive"))
      (node (ref "TF1") (pin "7") (pinfunction "DATA0_7") (pintype "passive"))
      (node (ref "U4") (pin "15") (pinfunction "GPIO26_15") (pintype "passive"))
    )
    (net (code "33") (name "/GPS_TX") (class "Default")
      (node (ref "AT1") (pin "3") (pinfunction "TX_3") (pintype "passive"))
      (node (ref "U4") (pin "5") (pinfunction "SENSOR_VP_5") (pintype "passive"))
    )
    (net (code "34") (name "/LCD_LEDK") (class "Default")
      (node (ref "LC1") (pin "8") (pinfunction "BL_K_8") (pintype "passive"))
      (node (ref "R15") (pin "2") (pinfunction "2_2") (pintype "passive"))
    )
    (net (code "35") (name "/PREVGH") (class "Default")
      (node (ref "C29") (pin "2") (pinfunction "2_2") (pintype "passive"))
      (node (ref "D11") (pin "1") (pinfunction "K_1") (pintype "passive"))
      (node (ref "EINK1") (pin "21") (pinfunction "PREVGH_21") (pintype "passive"))
    )
    (net (code "36") (name "/PREVGL") (class "Default")
      (node (ref "C31") (pin "2") (pinfunction "2_2") (pintype "passive"))
      (node (ref "D10") (pin "2") (pinfunction "A_2") (pintype "passive"))
      (node (ref "EINK1") (pin "23") (pinfunction "PREVGL_23") (pintype "passive"))
    )
    (net (code "37") (name "/RESE") (class "Default")
      (node (ref "EINK1") (pin "3") (pinfunction "RESE_3") (pintype "passive"))
      (node (ref "Q9") (pin "2") (pinfunction "S_2") (pintype "passive"))
      (node (ref "R24") (pin "2") (pinfunction "2_2") (pintype "passive"))
    )
    (net (code "38") (name "/RTS") (class "Default")
      (node (ref "Q3") (pin "1") (pinfunction "E1_1") (pintype "passive"))
      (node (ref "R12") (pin "1") (pinfunction "1_1") (pintype "passive"))
      (node (ref "U2") (pin "24") (pinfunction "RTS_24") (pintype "passive"))
    )
    (net (code "39") (name "/USB-PWR-D_N") (class "Default")
      (node (ref "U2") (pin "5") (pinfunction "D-_5") (pintype "passive"))
      (node (ref "USB1") (pin "A7") (pinfunction "D-_A7") (pintype "passive"))
      (node (ref "USB1") (pin "B7") (pinfunction "D-_B7") (pintype "passive"))
    )
    (net (code "40") (name "/USB-PWR-D_P") (class "Default")
      (node (ref "U2") (pin "4") (pinfunction "D+_4") (pintype "passive"))
      (node (ref "USB1") (pin "A6") (pinfunction "D+_A6") (pintype "passive"))
      (node (ref "USB1") (pin "B6") (pinfunction "D+_B6") (pintype "passive"))
    )
    (net (code "41") (name "/V_GPS") (class "Default")
      (node (ref "AT1") (pin "1") (pinfunction "VCC_1") (pintype "passive"))
      (node (ref "C12") (pin "1") (pinfunction "1_1") (pintype "passive"))
      (node (ref "C16") (pin "2") (pinfunction "2_2") (pintype "passive"))
      (node (ref "Q8") (pin "3") (pinfunction "D_3") (pintype "passive"))
      (node (ref "TP12") (pin "0") (pinfunction "0_0") (pintype "passive"))
      (node (ref "TP15") (pin "0") (pinfunction "0_0") (pintype "passive"))
      (node (ref "U5") (pin "13") (pinfunction "VDD_13") (pintype "passive"))
      (node (ref "U5") (pin "8") (pinfunction "VLogic_8") (pintype "passive"))
    )
    (net (code "42") (name "/V_LCD") (class "Default")
      (node (ref "C11") (pin "2") (pinfunction "2_2") (pintype "passive"))
      (node (ref "C13") (pin "2") (pinfunction "2_2") (pintype "passive"))
      (node (ref "CT1") (pin "6") (pinfunction "VCC_6") (pintype "passive"))
      (node (ref "LC1") (pin "2") (pinfunction "VCC_2") (pintype "passive"))
      (node (ref "LC1") (pin "7") (pinfunction "BL_A_7") (pintype "passive"))
      (node (ref "Q6") (pin "3") (pinfunction "D_3") (pintype "passive"))
      (node (ref "TP18") (pin "0") (pinfunction "0_0") (pintype "passive"))
    )
    (net (code "43") (name "3V3A") (class "Default")
      (node (ref "C5") (pin "2") (pinfunction "2_2") (pintype "passive"))
      (node (ref "C6") (pin "2") (pinfunction "2_2") (pintype "passive"))
      (node (ref "R13") (pin "1") (pinfunction "1_1") (pintype "passive"))
      (node (ref "R5") (pin "2") (pinfunction "2_2") (pintype "passive"))
      (node (ref "U4") (pin "1") (pinfunction "VDDA_1") (pintype "power_in"))
      (node (ref "U4") (pin "19") (pinfunction "VDD3P3_RTC_19") (pintype "power_in"))
      (node (ref "U4") (pin "3") (pinfunction "VDD3P3_3") (pintype "power_in"))
      (node (ref "U4") (pin "37") (pinfunction "VDD3P3_CPU_37") (pintype "power_in"))
      (node (ref "U4") (pin "4") (pinfunction "VDD3P3_4") (pintype "power_in"))
      (node (ref "U4") (pin "43") (pinfunction "VDDA_43") (pintype "power_in"))
      (node (ref "U4") (pin "46") (pinfunction "VDDA_46") (pintype "power_in"))
    )
    (net (code "44") (name "GND") (class "Default")
      (node (ref "AT1") (pin "2") (pinfunction "GND_2") (pintype "passive"))
      (node (ref "C1") (pin "1") (pinfunction "1_1") (pintype "passive"))
      (node (ref "C10") (pin "2") (pinfunction "2_2") (pintype "passive"))
      (node (ref "C11") (pin "1") (pinfunction "1_1") (pintype "passive"))
      (node (ref "C12") (pin "2") (pinfunction "2_2") (pintype "passive"))
      (node (ref "C13") (pin "1") (pinfunction "1_1") (pintype "passive"))
      (node (ref "C14") (pin "2") (pinfunction "2_2") (pintype "passive"))
      (node (ref "C15") (pin "1") (pinfunction "1_1") (pintype "passive"))
      (node (ref "C16") (pin "1") (pinfunction "1_1") (pintype "passive"))
      (node (ref "C17") (pin "1") (pinfunction "1_1") (pintype "passive"))
      (node (ref "C18") (pin "1") (pinfunction "1_1") (pintype "passive"))
      (node (ref "C19") (pin "1") (pinfunction "1_1") (pintype "passive"))
      (node (ref "C2") (pin "1") (pinfunction "1_1") (pintype "passive"))
      (node (ref "C20") (pin "1") (pinfunction "1_1") (pintype "passive"))
      (node (ref "C21") (pin "1") (pinfunction "1_1") (pintype "passive"))
      (node (ref "C22") (pin "1") (pinfunction "1_1") (pintype "passive"))
      (node (ref "C23") (pin "1") (pinfunction "1_1") (pintype "passive"))
      (node (ref "C25") (pin "1") (pinfunction "1_1") (pintype "passive"))
      (node (ref "C26") (pin "1") (pinfunction "1_1") (pintype "passive"))
      (node (ref "C27") (pin "1") (pinfunction "1_1") (pintype "passive"))
      (node (ref "C28") (pin "1") (pinfunction "1_1") (pintype "passive"))
      (node (ref "C29") (pin "1") (pinfunction "1_1") (pintype "passive"))
      (node (ref "C30") (pin "1") (pinfunction "1_1") (pintype "passive"))
      (node (ref "C31") (pin "1") (pinfunction "1_1") (pintype "passive"))
      (node (ref "C32") (pin "1") (pinfunction "1_1") (pintype "passive"))
      (node (ref "C4") (pin "1") (pinfunction "1_1") (pintype "passive"))
      (node (ref "C5") (pin "1") (pinfunction "1_1") (pintype "passive"))
      (node (ref "C6") (pin "1") (pinfunction "1_1") (pintype "passive"))
      (node (ref "C7") (pin "1") (pinfunction "1_1") (pintype "passive"))
      (node (ref "C8") (pin "1") (pinfunction "1_1") (pintype "passive"))
      (node (ref "C9") (pin "1") (pinfunction "1_1") (pintype "passive"))
      (node (ref "CT1") (pin "1") (pinfunction "GND_1") (pintype "passive"))
      (node (ref "D5") (pin "2") (pinfunction "K_2") (pintype "passive"))
      (node (ref "D9") (pin "1") (pinfunction "K_1") (pintype "passive"))
      (node (ref "EINK1") (pin "17") (pinfunction "VSS_17") (pintype "passive"))
      (node (ref "EINK1") (pin "8") (pinfunction "BS_8") (pintype "passive"))
      (node (ref "IC1") (pin "14") (pinfunction "TMR_14") (pintype "passive"))
      (node (ref "IC1") (pin "17") (pinfunction "GND_17") (pintype "passive"))
      (node (ref "IC1") (pin "6") (pinfunction "EN1_6") (pintype "passive"))
      (node (ref "IC1") (pin "8") (pinfunction "VSS_8") (pintype "passive"))
      (node (ref "IC2") (pin "3") (pinfunction "GND_3") (pintype "passive"))
      (node (ref "LC1") (pin "1") (pinfunction "GND_1") (pintype "passive"))
      (node (ref "P1") (pin "2") (pinfunction "2_2") (pintype "passive"))
      (node (ref "P3") (pin "4") (pinfunction "4_4") (pintype "passive"))
      (node (ref "P6") (pin "2") (pinfunction "2_2") (pintype "passive"))
      (node (ref "Q2") (pin "2") (pinfunction "S_2") (pintype "passive"))
      (node (ref "Q4") (pin "2") (pinfunction "S_2") (pintype "passive"))
      (node (ref "R10") (pin "1") (pinfunction "1_1") (pintype "passive"))
      (node (ref "R11") (pin "2") (pinfunction "2_2") (pintype "passive"))
      (node (ref "R14") (pin "1") (pinfunction "1_1") (pintype "passive"))
      (node (ref "R16") (pin "2") (pinfunction "2_2") (pintype "passive"))
      (node (ref "R17") (pin "1") (pinfunction "1_1") (pintype "passive"))
      (node (ref "R24") (pin "1") (pinfunction "1_1") (pintype "passive"))
      (node (ref "R31") (pin "1") (pinfunction "1_1") (pintype "passive"))
      (node (ref "R32") (pin "2") (pinfunction "2_2") (pintype "passive"))
      (node (ref "R36") (pin "1") (pinfunction "1_1") (pintype "passive"))
      (node (ref "R4") (pin "1") (pinfunction "1_1") (pintype "passive"))
      (node (ref "R7") (pin "1") (pinfunction "1_1") (pintype "passive"))
      (node (ref "R8") (pin "1") (pinfunction "1_1") (pintype "passive"))
      (node (ref "S1") (pin "2") (pinfunction "NO_2") (pintype "passive"))
      (node (ref "TF1") (pin "10") (pinfunction "GND_10") (pintype "passive"))
      (node (ref "TF1") (pin "6") (pinfunction "VSS_6") (pintype "passive"))
      (node (ref "TP10") (pin "0") (pinfunction "0_0") (pintype "passive"))
      (node (ref "TP3") (pin "0") (pinfunction "0_0") (pintype "passive"))
      (node (ref "U1") (pin "2") (pinfunction "GND_2") (pintype "passive"))
      (node (ref "U2") (pin "29") (pinfunction "HEAT_TAB_29") (pintype "passive"))
      (node (ref "U2") (pin "3") (pinfunction "GND_3") (pintype "passive"))
      (node (ref "U4") (pin "49") (pinfunction "GND_49") (pintype "power_in"))
      (node (ref "U5") (pin "1") (pinfunction "CLKIN_1") (pintype "passive"))
      (node (ref "U5") (pin "11") (pinfunction "FSYNC_11") (pintype "passive"))
      (node (ref "U5") (pin "18") (pinfunction "GND_18") (pintype "passive"))
      (node (ref "U5") (pin "9") (pinfunction "AD0_9") (pintype "passive"))
      (node (ref "USB1") (pin "1") (pinfunction "SH1_1") (pintype "passive"))
      (node (ref "USB1") (pin "2") (pinfunction "SH2_2") (pintype "passive"))
      (node (ref "USB1") (pin "3") (pinfunction "SH3_3") (pintype "passive"))
      (node (ref "USB1") (pin "4") (pinfunction "SH4_4") (pintype "passive"))
      (node (ref "USB1") (pin "A1") (pinfunction "GND_A1") (pintype "passive"))
      (node (ref "USB1") (pin "A12") (pinfunction "GND_A12") (pintype "passive"))
      (node (ref "USB1") (pin "B1") (pinfunction "GND_B1") (pintype "passive"))
      (node (ref "USB1") (pin "B12") (pinfunction "GND_B12") (pintype "passive"))
    )
    (net (code "45") (name "Net-(A1-Pad1)") (class "Default")
      (node (ref "A1") (pin "1") (pinfunction "1_1") (pintype "passive"))
      (node (ref "J1") (pin "1") (pinfunction "1_1") (pintype "passive"))
    )
    (net (code "46") (name "Net-(A2-Pad1)") (class "Default")
      (node (ref "A2") (pin "1") (pinfunction "1_1") (pintype "passive"))
      (node (ref "J2") (pin "1") (pinfunction "1_1") (pintype "passive"))
    )
    (net (code "47") (name "Net-(D1-A)") (class "Default")
      (node (ref "D1") (pin "1") (pinfunction "A_1") (pintype "passive"))
      (node (ref "Q1") (pin "1") (pinfunction "G_1") (pintype "passive"))
      (node (ref "Q2") (pin "3") (pinfunction "D_3") (pintype "passive"))
      (node (ref "R3") (pin "2") (pinfunction "2_2") (pintype "passive"))
    )
    (net (code "48") (name "Net-(D3-K)") (class "Default")
      (node (ref "D3") (pin "2") (pinfunction "K_2") (pintype "passive"))
      (node (ref "Q2") (pin "1") (pinfunction "G_1") (pintype "passive"))
      (node (ref "R7") (pin "2") (pinfunction "2_2") (pintype "passive"))
    )
    (net (code "49") (name "Net-(D5-A)") (class "Default")
      (node (ref "D5") (pin "1") (pinfunction "A_1") (pintype "passive"))
      (node (ref "R27") (pin "1") (pinfunction "1_1") (pintype "passive"))
    )
    (net (code "50") (name "Net-(D6-A)") (class "Default")
      (node (ref "D6") (pin "2") (pinfunction "A_2") (pintype "passive"))
      (node (ref "P6") (pin "1") (pinfunction "1_1") (pintype "passive"))
    )
    (net (code "51") (name "Net-(D7-K)") (class "Default")
      (node (ref "D7") (pin "2") (pinfunction "K_2") (pintype "passive"))
      (node (ref "R34") (pin "1") (pinfunction "1_1") (pintype "passive"))
    )
    (net (code "52") (name "Net-(D8-K)") (class "Default")
      (node (ref "D8") (pin "2") (pinfunction "K_2") (pintype "passive"))
      (node (ref "R35") (pin "1") (pinfunction "1_1") (pintype "passive"))
    )
    (net (code "53") (name "Net-(D10-K)") (class "Default")
      (node (ref "C24") (pin "1") (pinfunction "1_1") (pintype "passive"))
      (node (ref "D10") (pin "1") (pinfunction "K_1") (pintype "passive"))
      (node (ref "D9") (pin "2") (pinfunction "A_2") (pintype "passive"))
    )
    (net (code "54") (name "Net-(D11-A)") (class "Default")
      (node (ref "C24") (pin "2") (pinfunction "2_2") (pintype "passive"))
      (node (ref "D11") (pin "2") (pinfunction "A_2") (pintype "passive"))
      (node (ref "L1") (pin "2") (pinfunction "2_2") (pintype "passive"))
      (node (ref "Q9") (pin "3") (pinfunction "D_3") (pintype "passive"))
    )
    (net (code "55") (name "Net-(EINK1-VCOM)") (class "Default")
      (node (ref "C32") (pin "2") (pinfunction "2_2") (pintype "passive"))
      (node (ref "EINK1") (pin "24") (pinfunction "VCOM_24") (pintype "passive"))
    )
    (net (code "56") (name "Net-(EINK1-VDD)") (class "Default")
      (node (ref "C26") (pin "2") (pinfunction "2_2") (pintype "passive"))
      (node (ref "EINK1") (pin "18") (pinfunction "VDD_18") (pintype "passive"))
    )
    (net (code "57") (name "Net-(EINK1-VGH)") (class "Default")
      (node (ref "C22") (pin "2") (pinfunction "2_2") (pintype "passive"))
      (node (ref "EINK1") (pin "5") (pinfunction "VGH_5") (pintype "passive"))
    )
    (net (code "58") (name "Net-(EINK1-VGL)") (class "Default")
      (node (ref "C21") (pin "2") (pinfunction "2_2") (pintype "passive"))
      (node (ref "EINK1") (pin "4") (pinfunction "VGL_4") (pintype "passive"))
    )
    (net (code "59") (name "Net-(EINK1-VPP)") (class "Default")
      (node (ref "C27") (pin "2") (pinfunction "2_2") (pintype "passive"))
      (node (ref "EINK1") (pin "19") (pinfunction "VPP_19") (pintype "passive"))
    )
    (net (code "60") (name "Net-(EINK1-VSH)") (class "Default")
      (node (ref "C28") (pin "2") (pinfunction "2_2") (pintype "passive"))
      (node (ref "EINK1") (pin "20") (pinfunction "VSH_20") (pintype "passive"))
    )
    (net (code "61") (name "Net-(EINK1-VSL)") (class "Default")
      (node (ref "C30") (pin "2") (pinfunction "2_2") (pintype "passive"))
      (node (ref "EINK1") (pin "22") (pinfunction "VSL_22") (pintype "passive"))
    )
    (net (code "62") (name "Net-(IC1-ILIM)") (class "Default")
      (node (ref "IC1") (pin "12") (pinfunction "ILIM_12") (pintype "passive"))
      (node (ref "R31") (pin "2") (pinfunction "2_2") (pintype "passive"))
    )
    (net (code "63") (name "Net-(IC1-ISET)") (class "Default")
      (node (ref "IC1") (pin "16") (pinfunction "ISET_16") (pintype "passive"))
      (node (ref "R10") (pin "2") (pinfunction "2_2") (pintype "passive"))
    )
    (net (code "64") (name "Net-(IC1-TD)") (class "Default")
      (node (ref "IC1") (pin "15") (pinfunction "TD_15") (pintype "passive"))
      (node (ref "R8") (pin "2") (pinfunction "2_2") (pintype "passive"))
    )
    (net (code "65") (name "Net-(IC1-TS)") (class "Default")
      (node (ref "IC1") (pin "1") (pinfunction "TS_1") (pintype "passive"))
      (node (ref "R11") (pin "1") (pinfunction "1_1") (pintype "passive"))
    )
    (net (code "66") (name "Net-(IC1-~{CE})") (class "Default")
      (node (ref "IC1") (pin "4") (pinfunction "~{CE}_4") (pintype "passive"))
      (node (ref "R32") (pin "1") (pinfunction "1_1") (pintype "passive"))
      (node (ref "TP4") (pin "0") (pinfunction "0_0") (pintype "passive"))
    )
    (net (code "67") (name "Net-(IC1-~{PGOOD})") (class "Default")
      (node (ref "IC1") (pin "7") (pinfunction "~{PGOOD}_7") (pintype "passive"))
      (node (ref "R35") (pin "2") (pinfunction "2_2") (pintype "passive"))
    )
    (net (code "68") (name "Net-(Q3A-B1)") (class "Default")
      (node (ref "Q3") (pin "2") (pinfunction "B1_2") (pintype "passive"))
      (node (ref "R9") (pin "2") (pinfunction "2_2") (pintype "passive"))
    )
    (net (code "69") (name "Net-(Q3B-B2)") (class "Default")
      (node (ref "Q3") (pin "5") (pinfunction "B2_5") (pintype "passive"))
      (node (ref "R12") (pin "2") (pinfunction "2_2") (pintype "passive"))
    )
    (net (code "70") (name "Net-(Q4-D)") (class "Default")
      (node (ref "Q4") (pin "3") (pinfunction "D_3") (pintype "passive"))
      (node (ref "R15") (pin "1") (pinfunction "1_1") (pintype "passive"))
    )
    (net (code "71") (name "Net-(R19-Pad1)") (class "Default")
      (node (ref "R19") (pin "1") (pinfunction "1_1") (pintype "passive"))
      (node (ref "R38") (pin "1") (pinfunction "1_1") (pintype "passive"))
    )
    (net (code "72") (name "Net-(R20-Pad1)") (class "Default")
      (node (ref "R20") (pin "1") (pinfunction "1_1") (pintype "passive"))
      (node (ref "R39") (pin "1") (pinfunction "1_1") (pintype "passive"))
    )
    (net (code "73") (name "Net-(SW1-CH_A)") (class "Default")
      (node (ref "P4") (pin "4") (pinfunction "4_4") (pintype "passive"))
      (node (ref "SW1") (pin "1") (pinfunction "CH_A_1") (pintype "passive"))
    )
    (net (code "74") (name "Net-(SW1-CH_B)") (class "Default")
      (node (ref "P4") (pin "2") (pinfunction "2_2") (pintype "passive"))
      (node (ref "SW1") (pin "4") (pinfunction "CH_B_4") (pintype "passive"))
    )
    (net (code "75") (name "Net-(SW1-COM)") (class "Default")
      (node (ref "P4") (pin "1") (pinfunction "1_1") (pintype "passive"))
      (node (ref "SW1") (pin "3") (pinfunction "COM_3") (pintype "passive"))
      (node (ref "SW1") (pin "5") (pinfunction "GND_5") (pintype "passive"))
    )
    (net (code "76") (name "Net-(SW1-PUSH)") (class "Default")
      (node (ref "P4") (pin "3") (pinfunction "3_3") (pintype "passive"))
      (node (ref "SW1") (pin "2") (pinfunction "PUSH_2") (pintype "passive"))
    )
    (net (code "77") (name "Net-(U2-*RST)") (class "Default")
      (node (ref "R1") (pin "2") (pinfunction "2_2") (pintype "passive"))
      (node (ref "U2") (pin "9") (pinfunction "*RST_9") (pintype "passive"))
    )
    (net (code "78") (name "Net-(U2-TXD)") (class "Default")
      (node (ref "R6") (pin "2") (pinfunction "2_2") (pintype "passive"))
      (node (ref "U2") (pin "26") (pinfunction "TXD_26") (pintype "passive"))
    )
    (net (code "79") (name "Net-(U4-LNA_IN)") (class "Default")
      (node (ref "P2") (pin "1") (pinfunction "1_1") (pintype "passive"))
      (node (ref "U4") (pin "2") (pinfunction "LNA_IN_2") (pintype "passive"))
    )
    (net (code "80") (name "Net-(U5-CPOUT)") (class "Default")
      (node (ref "C15") (pin "2") (pinfunction "2_2") (pintype "passive"))
      (node (ref "U5") (pin "20") (pinfunction "CPOUT_20") (pintype "passive"))
    )
    (net (code "81") (name "Net-(U5-REGOUT)") (class "Default")
      (node (ref "C14") (pin "1") (pinfunction "1_1") (pintype "passive"))
      (node (ref "U5") (pin "10") (pinfunction "REGOUT_10") (pintype "passive"))
    )
    (net (code "82") (name "Net-(USB1-CC1)") (class "Default")
      (node (ref "R16") (pin "1") (pinfunction "1_1") (pintype "passive"))
      (node (ref "USB1") (pin "A5") (pinfunction "CC1_A5") (pintype "passive"))
    )
    (net (code "83") (name "Net-(USB1-CC2)") (class "Default")
      (node (ref "R14") (pin "2") (pinfunction "2_2") (pintype "passive"))
      (node (ref "USB1") (pin "B5") (pinfunction "CC2_B5") (pintype "passive"))
    )
    (net (code "84") (name "VBAT") (class "Default")
      (node (ref "C18") (pin "2") (pinfunction "2_2") (pintype "passive"))
      (node (ref "C19") (pin "2") (pinfunction "2_2") (pintype "passive"))
      (node (ref "C20") (pin "2") (pinfunction "2_2") (pintype "passive"))
      (node (ref "D7") (pin "1") (pinfunction "A_1") (pintype "passive"))
      (node (ref "D8") (pin "1") (pinfunction "A_1") (pintype "passive"))
      (node (ref "IC1") (pin "10") (pinfunction "OUT_1_10") (pintype "passive"))
      (node (ref "IC1") (pin "11") (pinfunction "OUT_2_11") (pintype "passive"))
      (node (ref "IC1") (pin "5") (pinfunction "EN2_5") (pintype "passive"))
      (node (ref "Q1") (pin "2") (pinfunction "S_2") (pintype "passive"))
      (node (ref "R3") (pin "1") (pinfunction "1_1") (pintype "passive"))
    )
    (net (code "85") (name "VBAT_IN") (class "Default")
      (node (ref "C17") (pin "2") (pinfunction "2_2") (pintype "passive"))
      (node (ref "C9") (pin "2") (pinfunction "2_2") (pintype "passive"))
      (node (ref "IC1") (pin "2") (pinfunction "BAT_1_2") (pintype "passive"))
      (node (ref "IC1") (pin "3") (pinfunction "BAT_2_3") (pintype "passive"))
      (node (ref "P1") (pin "1") (pinfunction "1_1") (pintype "passive"))
    )
    (net (code "86") (name "VBUS") (class "Default")
      (node (ref "C7") (pin "2") (pinfunction "2_2") (pintype "passive"))
      (node (ref "C8") (pin "2") (pinfunction "2_2") (pintype "passive"))
      (node (ref "D4") (pin "1") (pinfunction "K_1") (pintype "passive"))
      (node (ref "D6") (pin "1") (pinfunction "K_1") (pintype "passive"))
      (node (ref "IC1") (pin "13") (pinfunction "IN_13") (pintype "passive"))
    )
    (net (code "87") (name "VCC_3V3") (class "Default")
      (node (ref "C1") (pin "2") (pinfunction "2_2") (pintype "passive"))
      (node (ref "C2") (pin "2") (pinfunction "2_2") (pintype "passive"))
      (node (ref "C23") (pin "2") (pinfunction "2_2") (pintype "passive"))
      (node (ref "C25") (pin "2") (pinfunction "2_2") (pintype "passive"))
      (node (ref "EINK1") (pin "15") (pinfunction "VDDIO_15") (pintype "passive"))
      (node (ref "EINK1") (pin "16") (pinfunction "VCI_16") (pintype "passive"))
      (node (ref "IC2") (pin "5") (pinfunction "VCC_5") (pintype "passive"))
      (node (ref "L1") (pin "1") (pinfunction "1_1") (pintype "passive"))
      (node (ref "Q6") (pin "2") (pinfunction "S_2") (pintype "passive"))
      (node (ref "Q8") (pin "2") (pinfunction "S_2") (pintype "passive"))
      (node (ref "R18") (pin "1") (pinfunction "1_1") (pintype "passive"))
      (node (ref "R19") (pin "2") (pinfunction "2_2") (pintype "passive"))
      (node (ref "R20") (pin "2") (pinfunction "2_2") (pintype "passive"))
      (node (ref "R21") (pin "1") (pinfunction "1_1") (pintype "passive"))
      (node (ref "R22") (pin "1") (pinfunction "1_1") (pintype "passive"))
      (node (ref "R23") (pin "1") (pinfunction "1_1") (pintype "passive"))
      (node (ref "R25") (pin "1") (pinfunction "1_1") (pintype "passive"))
      (node (ref "R26") (pin "1") (pinfunction "1_1") (pintype "passive"))
      (node (ref "R27") (pin "2") (pinfunction "2_2") (pintype "passive"))
      (node (ref "R28") (pin "2") (pinfunction "2_2") (pintype "passive"))
      (node (ref "R30") (pin "2") (pinfunction "2_2") (pintype "passive"))
      (node (ref "R5") (pin "1") (pinfunction "1_1") (pintype "passive"))
      (node (ref "TF1") (pin "4") (pinfunction "VDD_4") (pintype "passive"))
      (node (ref "TP1") (pin "0") (pinfunction "0_0") (pintype "passive"))
      (node (ref "TP2") (pin "0") (pinfunction "0_0") (pintype "passive"))
      (node (ref "U1") (pin "5") (pinfunction "VOUT_5") (pintype "passive"))
    )
    (net (code "88") (name "VIN") (class "Default")
      (node (ref "Q1") (pin "3") (pinfunction "D_3") (pintype "passive"))
      (node (ref "R2") (pin "2") (pinfunction "2_2") (pintype "passive"))
      (node (ref "U1") (pin "1") (pinfunction "VIN_1") (pintype "passive"))
      (node (ref "U1") (pin "3") (pinfunction "ON/OFF_3") (pintype "passive"))
    )
    (net (code "89") (name "VUSB") (class "Default")
      (node (ref "D4") (pin "2") (pinfunction "A_2") (pintype "passive"))
      (node (ref "R1") (pin "1") (pinfunction "1_1") (pintype "passive"))
      (node (ref "U2") (pin "7") (pinfunction "REGIN_7") (pintype "passive"))
      (node (ref "U2") (pin "8") (pinfunction "VBUS_8") (pintype "passive"))
      (node (ref "USB1") (pin "A4") (pinfunction "VBUS_A4") (pintype "passive"))
      (node (ref "USB1") (pin "A9") (pinfunction "VBUS_A9") (pintype "passive"))
      (node (ref "USB1") (pin "B4") (pinfunction "VBUS_B4") (pintype "passive"))
      (node (ref "USB1") (pin "B9") (pinfunction "VBUS_B9") (pintype "passive"))
    )
    (net (code "90") (name "unconnected-(AT1-PPS-Pad5)") (class "Default")
      (node (ref "AT1") (pin "5") (pinfunction "PPS_5") (pintype "passive+no_connect"))
    )
    (net (code "91") (name "unconnected-(EINK1-HLT_CTL-Pad1)") (class "Default")
      (node (ref "EINK1") (pin "1") (pinfunction "HLT_CTL_1") (pintype "passive+no_connect"))
    )
    (net (code "92") (name "unconnected-(EINK1-TSCL-Pad6)") (class "Default")
      (node (ref "EINK1") (pin "6") (pinfunction "TSCL_6") (pintype "passive+no_connect"))
    )
    (net (code "93") (name "unconnected-(EINK1-TSDA-Pad7)") (class "Default")
      (node (ref "EINK1") (pin "7") (pinfunction "TSDA_7") (pintype "passive+no_connect"))
    )
    (net (code "94") (name "unconnected-(IC2-NC-Pad1)") (class "Default")
      (node (ref "IC2") (pin "1") (pinfunction "NC_1") (pintype "passive+no_connect"))
    )
    (net (code "95") (name "unconnected-(LC1-NC-Pad9)") (class "Default")
      (node (ref "LC1") (pin "9") (pinfunction "NC_9") (pintype "passive+no_connect"))
    )
    (net (code "96") (name "unconnected-(TF1-DATA1-Pad8)") (class "Default")
      (node (ref "TF1") (pin "8") (pinfunction "DATA1_8") (pintype "passive+no_connect"))
    )
    (net (code "97") (name "unconnected-(TF1-DATA2-Pad1)") (class "Default")
      (node (ref "TF1") (pin "1") (pinfunction "DATA2_1") (pintype "passive+no_connect"))
    )
    (net (code "98") (name "unconnected-(U1-BYPASS-Pad4)") (class "Default")
      (node (ref "U1") (pin "4") (pinfunction "BYPASS_4") (pintype "passive+no_connect"))
    )
    (net (code "99") (name "unconnected-(U2-*SUSPEND-Pad11)") (class "Default")
      (node (ref "U2") (pin "11") (pinfunction "*SUSPEND_11") (pintype "passive+no_connect"))
    )
    (net (code "100") (name "unconnected-(U2-CTS-Pad23)") (class "Default")
      (node (ref "U2") (pin "23") (pinfunction "CTS_23") (pintype "passive+no_connect"))
    )
    (net (code "101") (name "unconnected-(U2-DCD-Pad1)") (class "Default")
      (node (ref "U2") (pin "1") (pinfunction "DCD_1") (pintype "passive+no_connect"))
    )
    (net (code "102") (name "unconnected-(U2-DSR-Pad27)") (class "Default")
      (node (ref "U2") (pin "27") (pinfunction "DSR_27") (pintype "passive+no_connect"))
    )
    (net (code "103") (name "unconnected-(U2-NC-Pad10)") (class "Default")
      (node (ref "U2") (pin "10") (pinfunction "NC_10") (pintype "passive+no_connect"))
    )
    (net (code "104") (name "unconnected-(U2-NC-Pad13)") (class "Default")
      (node (ref "U2") (pin "13") (pinfunction "NC_13") (pintype "passive+no_connect"))
    )
    (net (code "105") (name "unconnected-(U2-NC-Pad14)") (class "Default")
      (node (ref "U2") (pin "14") (pinfunction "NC_14") (pintype "passive+no_connect"))
    )
    (net (code "106") (name "unconnected-(U2-NC-Pad15)") (class "Default")
      (node (ref "U2") (pin "15") (pinfunction "NC_15") (pintype "passive+no_connect"))
    )
    (net (code "107") (name "unconnected-(U2-NC-Pad16)") (class "Default")
      (node (ref "U2") (pin "16") (pinfunction "NC_16") (pintype "passive+no_connect"))
    )
    (net (code "108") (name "unconnected-(U2-NC-Pad17)") (class "Default")
      (node (ref "U2") (pin "17") (pinfunction "NC_17") (pintype "passive+no_connect"))
    )
    (net (code "109") (name "unconnected-(U2-NC-Pad18)") (class "Default")
      (node (ref "U2") (pin "18") (pinfunction "NC_18") (pintype "passive+no_connect"))
    )
    (net (code "110") (name "unconnected-(U2-NC-Pad19)") (class "Default")
      (node (ref "U2") (pin "19") (pinfunction "NC_19") (pintype "passive+no_connect"))
    )
    (net (code "111") (name "unconnected-(U2-NC-Pad20)") (class "Default")
      (node (ref "U2") (pin "20") (pinfunction "NC_20") (pintype "passive+no_connect"))
    )
    (net (code "112") (name "unconnected-(U2-NC-Pad21)") (class "Default")
      (node (ref "U2") (pin "21") (pinfunction "NC_21") (pintype "passive+no_connect"))
    )
    (net (code "113") (name "unconnected-(U2-NC-Pad22)") (class "Default")
      (node (ref "U2") (pin "22") (pinfunction "NC_22") (pintype "passive+no_connect"))
    )
    (net (code "114") (name "unconnected-(U2-RI-Pad2)") (class "Default")
      (node (ref "U2") (pin "2") (pinfunction "RI_2") (pintype "passive+no_connect"))
    )
    (net (code "115") (name "unconnected-(U2-SUSPEND-Pad12)") (class "Default")
      (node (ref "U2") (pin "12") (pinfunction "SUSPEND_12") (pintype "passive+no_connect"))
    )
    (net (code "116") (name "unconnected-(U2-VDD-Pad6)") (class "Default")
      (node (ref "U2") (pin "6") (pinfunction "VDD_6") (pintype "passive+no_connect"))
    )
    (net (code "117") (name "unconnected-(U4-CAP1_NC-Pad48)") (class "Default")
      (node (ref "U4") (pin "48") (pinfunction "CAP1_NC_48") (pintype "passive+no_connect"))
    )
    (net (code "118") (name "unconnected-(U4-CAP2_NC-Pad47)") (class "Default")
      (node (ref "U4") (pin "47") (pinfunction "CAP2_NC_47") (pintype "passive+no_connect"))
    )
    (net (code "119") (name "unconnected-(U4-IO16(FLASH_CS)-Pad25)") (class "Default")
      (node (ref "U4") (pin "25") (pinfunction "IO16(FLASH_CS)_25") (pintype "passive+no_connect"))
    )
    (net (code "120") (name "unconnected-(U4-IO17(FLASH_SD0)-Pad27)") (class "Default")
      (node (ref "U4") (pin "27") (pinfunction "IO17(FLASH_SD0)_27") (pintype "passive+no_connect"))
    )
    (net (code "121") (name "unconnected-(U4-SD_CLK(FLASH_CLK)-Pad31)") (class "Default")
      (node (ref "U4") (pin "31") (pinfunction "SD_CLK(FLASH_CLK)_31") (pintype "passive+no_connect"))
    )
    (net (code "122") (name "unconnected-(U4-SD_CMD(FLASH_SD2)-Pad30)") (class "Default")
      (node (ref "U4") (pin "30") (pinfunction "SD_CMD(FLASH_SD2)_30") (pintype "passive+no_connect"))
    )
    (net (code "123") (name "unconnected-(U4-SD_DATA_0(FLASH_SD3)-Pad32)") (class "Default")
      (node (ref "U4") (pin "32") (pinfunction "SD_DATA_0(FLASH_SD3)_32") (pintype "passive+no_connect"))
    )
    (net (code "124") (name "unconnected-(U4-SD_DATA_1(FLASH_SD1)-Pad33)") (class "Default")
      (node (ref "U4") (pin "33") (pinfunction "SD_DATA_1(FLASH_SD1)_33") (pintype "passive+no_connect"))
    )
    (net (code "125") (name "unconnected-(U4-VDD_SDIO_NC-Pad26)") (class "Default")
      (node (ref "U4") (pin "26") (pinfunction "VDD_SDIO_NC_26") (pintype "passive+no_connect"))
    )
    (net (code "126") (name "unconnected-(U4-XTAL_N_NC-Pad44)") (class "Default")
      (node (ref "U4") (pin "44") (pinfunction "XTAL_N_NC_44") (pintype "passive+no_connect"))
    )
    (net (code "127") (name "unconnected-(U4-XTAL_P_NC-Pad45)") (class "Default")
      (node (ref "U4") (pin "45") (pinfunction "XTAL_P_NC_45") (pintype "passive+no_connect"))
    )
    (net (code "128") (name "unconnected-(U5-A_CL-Pad7)") (class "Default")
      (node (ref "U5") (pin "7") (pinfunction "A_CL_7") (pintype "passive+no_connect"))
    )
    (net (code "129") (name "unconnected-(U5-A_DA-Pad6)") (class "Default")
      (node (ref "U5") (pin "6") (pinfunction "A_DA_6") (pintype "passive+no_connect"))
    )
    (net (code "130") (name "unconnected-(U5-CLKOUT-Pad22)") (class "Default")
      (node (ref "U5") (pin "22") (pinfunction "CLKOUT_22") (pintype "passive+no_connect"))
    )
    (net (code "131") (name "unconnected-(U5-INT-Pad12)") (class "Default")
      (node (ref "U5") (pin "12") (pinfunction "INT_12") (pintype "passive+no_connect"))
    )
    (net (code "132") (name "unconnected-(U5-NC-Pad2)") (class "Default")
      (node (ref "U5") (pin "2") (pinfunction "NC_2") (pintype "passive+no_connect"))
    )
    (net (code "133") (name "unconnected-(U5-NC-Pad3)") (class "Default")
      (node (ref "U5") (pin "3") (pinfunction "NC_3") (pintype "passive+no_connect"))
    )
    (net (code "134") (name "unconnected-(U5-NC-Pad4)") (class "Default")
      (node (ref "U5") (pin "4") (pinfunction "NC_4") (pintype "passive+no_connect"))
    )
    (net (code "135") (name "unconnected-(U5-NC-Pad5)") (class "Default")
      (node (ref "U5") (pin "5") (pinfunction "NC_5") (pintype "passive+no_connect"))
    )
    (net (code "136") (name "unconnected-(U5-NC-Pad14)") (class "Default")
      (node (ref "U5") (pin "14") (pinfunction "NC_14") (pintype "passive+no_connect"))
    )
    (net (code "137") (name "unconnected-(U5-NC-Pad15)") (class "Default")
      (node (ref "U5") (pin "15") (pinfunction "NC_15") (pintype "passive+no_connect"))
    )
    (net (code "138") (name "unconnected-(U5-NC-Pad16)") (class "Default")
      (node (ref "U5") (pin "16") (pinfunction "NC_16") (pintype "passive+no_connect"))
    )
    (net (code "139") (name "unconnected-(U5-NC-Pad17)") (class "Default")
      (node (ref "U5") (pin "17") (pinfunction "NC_17") (pintype "passive+no_connect"))
    )
    (net (code "140") (name "unconnected-(U5-RESV-Pad19)") (class "Default")
      (node (ref "U5") (pin "19") (pinfunction "RESV_19") (pintype "passive+no_connect"))
    )
    (net (code "141") (name "unconnected-(U5-RESV-Pad21)") (class "Default")
      (node (ref "U5") (pin "21") (pinfunction "RESV_21") (pintype "passive+no_connect"))
    )
    (net (code "142") (name "unconnected-(USB1-RX1+-PadB11)") (class "Default")
      (node (ref "USB1") (pin "B11") (pinfunction "RX1+_B11") (pintype "passive+no_connect"))
    )
    (net (code "143") (name "unconnected-(USB1-RX1--PadB10)") (class "Default")
      (node (ref "USB1") (pin "B10") (pinfunction "RX1-_B10") (pintype "passive+no_connect"))
    )
    (net (code "144") (name "unconnected-(USB1-RX2+-PadA11)") (class "Default")
      (node (ref "USB1") (pin "A11") (pinfunction "RX2+_A11") (pintype "passive+no_connect"))
    )
    (net (code "145") (name "unconnected-(USB1-RX2--PadA10)") (class "Default")
      (node (ref "USB1") (pin "A10") (pinfunction "RX2-_A10") (pintype "passive+no_connect"))
    )
    (net (code "146") (name "unconnected-(USB1-SBU1-PadA8)") (class "Default")
      (node (ref "USB1") (pin "A8") (pinfunction "SBU1_A8") (pintype "passive+no_connect"))
    )
    (net (code "147") (name "unconnected-(USB1-SBU2-PadB8)") (class "Default")
      (node (ref "USB1") (pin "B8") (pinfunction "SBU2_B8") (pintype "passive+no_connect"))
    )
    (net (code "148") (name "unconnected-(USB1-TX1+-PadA2)") (class "Default")
      (node (ref "USB1") (pin "A2") (pinfunction "TX1+_A2") (pintype "passive+no_connect"))
    )
    (net (code "149") (name "unconnected-(USB1-TX1--PadA3)") (class "Default")
      (node (ref "USB1") (pin "A3") (pinfunction "TX1-_A3") (pintype "passive+no_connect"))
    )
    (net (code "150") (name "unconnected-(USB1-TX2+-PadB2)") (class "Default")
      (node (ref "USB1") (pin "B2") (pinfunction "TX2+_B2") (pintype "passive+no_connect"))
    )
    (net (code "151") (name "unconnected-(USB1-TX2--PadB3)") (class "Default")
      (node (ref "USB1") (pin "B3") (pinfunction "TX2-_B3") (pintype "passive+no_connect"))
    )
  )
)
